# AstroEQ_SMD_MK2_EQ5.net
KiCad netlist of a schematic drawn in EAGLE
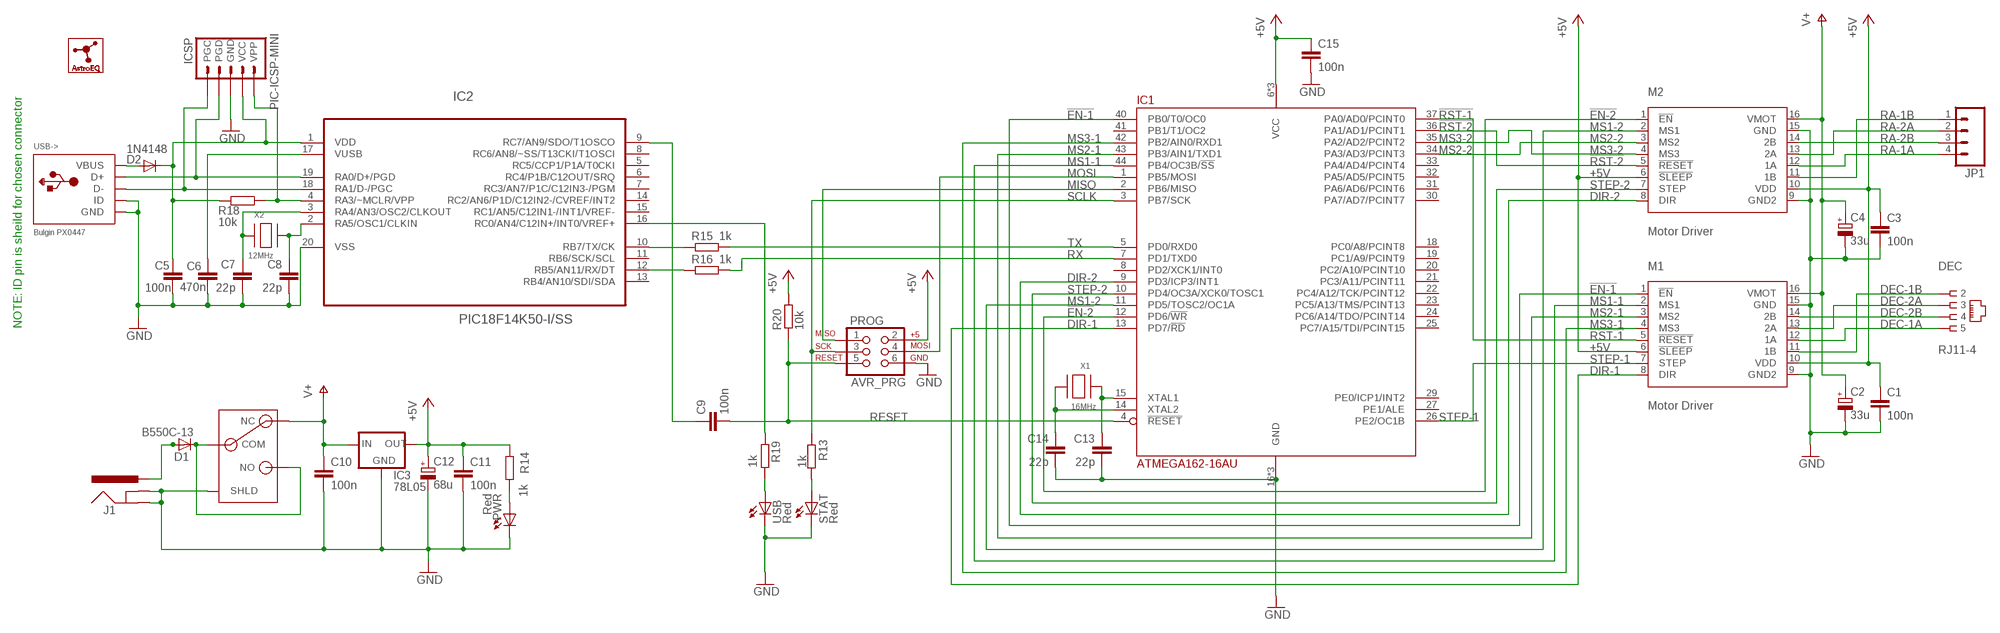
[diagram p0: schematic, sheet 1]

(export (version "E")
  (design (tool "Eeschema 10.0.6"))
  (components
    (comp (ref "C1")
      (value "100n")
      (footprint "eagle-import:C0603")
      (fields (field (name "MF") "MULTICOMP") (field (name "MPN") "T0603F104ZCT"))
      (libsource (lib "eagle-import") (part "resistor_C-EUC0603"))
    )
    (comp (ref "C2")
      (value "33u")
      (footprint "eagle-import:C_6032-28R")
      (fields (field (name "MF") "KEMET") (field (name "MPN") "T491C336K025AT"))
      (libsource (lib "eagle-import") (part "CPOL-EUC/6032-28R"))
    )
    (comp (ref "C3")
      (value "100n")
      (footprint "eagle-import:C0603")
      (fields (field (name "MF") "MULTICOMP") (field (name "MPN") "T0603F104ZCT"))
      (libsource (lib "eagle-import") (part "resistor_C-EUC0603"))
    )
    (comp (ref "C4")
      (value "33u")
      (footprint "eagle-import:C_6032-28R")
      (fields (field (name "MF") "KEMET") (field (name "MPN") "T491C336K025AT"))
      (libsource (lib "eagle-import") (part "CPOL-EUC/6032-28R"))
    )
    (comp (ref "C5")
      (value "100n")
      (footprint "eagle-import:C0603")
      (fields (field (name "MF") "MULTICOMP") (field (name "MPN") "T0603F104ZCT"))
      (libsource (lib "eagle-import") (part "resistor_C-EUC0603"))
    )
    (comp (ref "C6")
      (value "470n")
      (footprint "eagle-import:C0603")
      (fields (field (name "MF") "MURATA") (field (name "MPN") "GRM188R61C474KA93D"))
      (libsource (lib "eagle-import") (part "C-EUC0603"))
    )
    (comp (ref "C7")
      (value "22p")
      (footprint "eagle-import:C0603")
      (fields (field (name "MF") "MULTICOMP") (field (name "MPN") "U0603C220JCT"))
      (libsource (lib "eagle-import") (part "C-EUC0603"))
    )
    (comp (ref "C8")
      (value "22p")
      (footprint "eagle-import:C0603")
      (fields (field (name "MF") "MULTICOMP") (field (name "MPN") "U0603C220JCT"))
      (libsource (lib "eagle-import") (part "C-EUC0603"))
    )
    (comp (ref "C9")
      (value "100n")
      (footprint "eagle-import:C0603")
      (fields (field (name "MF") "MULTICOMP") (field (name "MPN") "T0603F104ZCT"))
      (libsource (lib "eagle-import") (part "resistor_C-EUC0603"))
    )
    (comp (ref "C10")
      (value "100n")
      (footprint "eagle-import:C0603")
      (fields (field (name "MF") "MULTICOMP") (field (name "MPN") "T0603F104ZCT"))
      (libsource (lib "eagle-import") (part "resistor_C-EUC0603"))
    )
    (comp (ref "C11")
      (value "100n")
      (footprint "eagle-import:C0603")
      (fields (field (name "MF") "MULTICOMP") (field (name "MPN") "T0603F104ZCT"))
      (libsource (lib "eagle-import") (part "resistor_C-EUC0603"))
    )
    (comp (ref "C12")
      (value "68u")
      (footprint "eagle-import:C_6032-28R")
      (fields (field (name "MF") "AVX") (field (name "MPN") "TPSC686K016R0125"))
      (libsource (lib "eagle-import") (part "CPOL-EUC/6032-28R"))
    )
    (comp (ref "C13")
      (value "22p")
      (footprint "eagle-import:C0603")
      (fields (field (name "MF") "MULTICOMP") (field (name "MPN") "U0603C220JCT"))
      (libsource (lib "eagle-import") (part "C-EUC0603"))
    )
    (comp (ref "C14")
      (value "22p")
      (footprint "eagle-import:C0603")
      (fields (field (name "MF") "MULTICOMP") (field (name "MPN") "U0603C220JCT"))
      (libsource (lib "eagle-import") (part "C-EUC0603"))
    )
    (comp (ref "C15")
      (value "100n")
      (footprint "eagle-import:C0603")
      (fields (field (name "MF") "MULTICOMP") (field (name "MPN") "T0603F104ZCT"))
      (libsource (lib "eagle-import") (part "resistor_C-EUC0603"))
    )
    (comp (ref "D1")
      (value "B550C-13")
      (footprint "eagle-import:SMC")
      (fields (field (name "MF") "DIODES INC.") (field (name "MPN") "B550C-13-F"))
      (libsource (lib "eagle-import") (part "DIODE-SMC"))
    )
    (comp (ref "D2")
      (value "1N4148")
      (footprint "eagle-import:SOD-323")
      (fields (field (name "MF") "VISHAY SEMICONDUCTOR") (field (name "MPN") "1N4148WS-V-GS08"))
      (libsource (lib "eagle-import") (part "DIODESOD"))
    )
    (comp (ref "DEC")
      (value "RJ11-4")
      (footprint "eagle-import:RJ11-NO_SHIELD-4")
      (fields (field (name "MF") "MOLEX") (field (name "MPN") "95503-2641"))
      (libsource (lib "eagle-import") (part "RJ11-4"))
    )
    (comp (ref "IC1")
      (value "ATMEGA162-16AU")
      (footprint "eagle-import:TQFP44")
      (fields (field (name "MF") "ATMEL"))
      (libsource (lib "eagle-import") (part "ATMEGA162-16AU"))
    )
    (comp (ref "IC2")
      (value "PIC18F14K50-I/SS")
      (footprint "eagle-import:SS20")
      (fields
        (field (name "MPN") "PIC18F14K50")
        (field (name "MF") "MICROCHIP")
        (field (name "MPN_1") "PIC18F14K50-I/SS")
        (field (name "OC_FARNELL") "1648504")
        (field (name "PACKAGE") "SSOP20")
      )
      (libsource (lib "eagle-import") (part "PIC18F14K50-I/SS"))
    )
    (comp (ref "IC3")
      (value "78L05")
      (footprint "eagle-import:SOT23")
      (fields (field (name "MF") "TAIWAN SEMICONDUCTOR") (field (name "MPN") "TS78L05CX RF"))
      (libsource (lib "eagle-import") (part "78LXXSOT-23"))
    )
    (comp (ref "ICSP")
      (value "PIC-ICSP-MINI")
      (footprint "eagle-import:PIC-ICSP-MINI")
      (fields (field (name "MF") "HARWIN") (field (name "MPN") "M52-5000545"))
      (libsource (lib "eagle-import") (part "PIC-ICSP-MINI"))
    )
    (comp (ref "J1")
      (value "POWER_JACKPANEL")
      (footprint "eagle-import:POWER_JACK_PANEL")
      (fields (field (name "MF") "SWITCHCRAFT") (field (name "MPN") "PCL712AS"))
      (libsource (lib "eagle-import") (part "POWER_JACKPANEL"))
    )
    (comp (ref "JP1")
      (value "M04POLAR")
      (footprint "eagle-import:MOLEX-1X4")
      (fields (field (name "MF") "MULTICOMP") (field (name "MPN") "MC34645"))
      (libsource (lib "eagle-import") (part "M04POLAR"))
    )
    (comp (ref "LOGO1")
      (value "ASTROEQ5MM")
      (footprint "eagle-import:ASTROEQ-SMALL")
      (libsource (lib "eagle-import") (part "ASTROEQ5MM"))
    )
    (comp (ref "M1")
      (value "Motor Driver")
      (footprint "eagle-import:DIP16-W")
      (libsource (lib "eagle-import") (part "A4983CARRIER"))
    )
    (comp (ref "M2")
      (value "Motor Driver")
      (footprint "eagle-import:DIP16-W")
      (libsource (lib "eagle-import") (part "A4983CARRIER"))
    )
    (comp (ref "PROG")
      (value "AVR_PRG")
      (footprint "eagle-import:2X3")
      (fields (field (name "MF") "TE CONNECTIVITY / AMP") (field (name "MPN") "826632-3"))
      (libsource (lib "eagle-import") (part "AVR_SPI_PRG_6PTH"))
    )
    (comp (ref "PWR")
      (value "Red")
      (footprint "eagle-import:LED3MM")
      (fields (field (name "MF") "KINGBRIGHT") (field (name "MPN") "L-424HDT"))
      (libsource (lib "eagle-import") (part "LED3MM"))
    )
    (comp (ref "R13")
      (value "1k")
      (footprint "eagle-import:R0603")
      (fields (field (name "MF") "PANASONIC") (field (name "MPN") "ERJ3GEYJ102V"))
      (libsource (lib "eagle-import") (part "rcl_R-EU_R0603"))
    )
    (comp (ref "R14")
      (value "1k")
      (footprint "eagle-import:R0603")
      (fields (field (name "MF") "PANASONIC") (field (name "MPN") "ERJ3GEYJ102V"))
      (libsource (lib "eagle-import") (part "rcl_R-EU_R0603"))
    )
    (comp (ref "R15")
      (value "1k")
      (footprint "eagle-import:R0603")
      (fields (field (name "MF") "PANASONIC") (field (name "MPN") "ERJ3GEYJ102V"))
      (libsource (lib "eagle-import") (part "R-EU_R0603"))
    )
    (comp (ref "R16")
      (value "1k")
      (footprint "eagle-import:R0603")
      (fields (field (name "MF") "PANASONIC") (field (name "MPN") "ERJ3GEYJ102V"))
      (libsource (lib "eagle-import") (part "R-EU_R0603"))
    )
    (comp (ref "R18")
      (value "10k")
      (footprint "eagle-import:R0603")
      (fields (field (name "MF") "PANASONIC") (field (name "MPN") "ERJ3GEYJ103V"))
      (libsource (lib "eagle-import") (part "rcl_R-EU_R0603"))
    )
    (comp (ref "R19")
      (value "1k")
      (footprint "eagle-import:R0603")
      (fields (field (name "MF") "PANASONIC") (field (name "MPN") "ERJ3GEYJ102V"))
      (libsource (lib "eagle-import") (part "rcl_R-EU_R0603"))
    )
    (comp (ref "R20")
      (value "10k")
      (footprint "eagle-import:R0603")
      (fields (field (name "MF") "PANASONIC") (field (name "MPN") "ERJ3GEYJ103V"))
      (libsource (lib "eagle-import") (part "rcl_R-EU_R0603"))
    )
    (comp (ref "STAT")
      (value "Red")
      (footprint "eagle-import:LED3MM")
      (fields (field (name "MF") "KINGBRIGHT") (field (name "MPN") "L-424HDT"))
      (libsource (lib "eagle-import") (part "LED3MM"))
    )
    (comp (ref "SW1")
      (value "SWITCH")
      (footprint "eagle-import:SPST")
      (fields (field (name "MF") "TE CONNECTIVITY") (field (name "MPN") "AE101J1V3B004"))
      (libsource (lib "eagle-import") (part "SWITCH"))
    )
    (comp (ref "USB")
      (value "Red")
      (footprint "eagle-import:LED3MM")
      (fields (field (name "MF") "KINGBRIGHT") (field (name "MPN") "L-424HDT"))
      (libsource (lib "eagle-import") (part "LED3MM"))
    )
    (comp (ref "USB->")
      (value "Bulgin PX0447")
      (footprint "eagle-import:USB-MINIB-BULGIN")
      (fields (field (name "MF") "BULGIN") (field (name "MPN") "PX0447"))
      (libsource (lib "eagle-import") (part "USBBULGIN"))
    )
    (comp (ref "X1")
      (value "16MHz")
      (footprint "eagle-import:NX5032")
      (fields (field (name "MF") "TXC") (field (name "MPN") "7A-16.000MAAJ-T"))
      (libsource (lib "eagle-import") (part "XTALNX5032"))
    )
    (comp (ref "X2")
      (value "12MHz")
      (footprint "eagle-import:NX5032")
      (fields (field (name "MF") "TXC") (field (name "MPN") "7A-12.000MAAJ-T"))
      (libsource (lib "eagle-import") (part "XTALNX5032"))
    )
  )
  (nets
    (net (code "1") (name "+5V") (class "Default")
      (node (ref "C1") (pin "1") (pinfunction "1_1") (pintype "passive"))
      (node (ref "C11") (pin "1") (pinfunction "1_1") (pintype "passive"))
      (node (ref "C12") (pin "+") (pinfunction "+_+") (pintype "passive"))
      (node (ref "C15") (pin "1") (pinfunction "1_1") (pintype "passive"))
      (node (ref "C3") (pin "1") (pinfunction "1_1") (pintype "passive"))
      (node (ref "IC1") (pin "17") (pinfunction "VCC_17") (pintype "power_in"))
      (node (ref "IC1") (pin "38") (pinfunction "VCC_38") (pintype "power_in"))
      (node (ref "IC1") (pin "6") (pinfunction "VCC_6") (pintype "power_in"))
      (node (ref "IC3") (pin "1") (pinfunction "OUT_1") (pintype "passive"))
      (node (ref "M1") (pin "10") (pinfunction "VDD_10") (pintype "power_in"))
      (node (ref "M1") (pin "6") (pinfunction "~{SLEEP}_6") (pintype "input"))
      (node (ref "M2") (pin "10") (pinfunction "VDD_10") (pintype "power_in"))
      (node (ref "M2") (pin "6") (pinfunction "~{SLEEP}_6") (pintype "input"))
      (node (ref "PROG") (pin "2") (pinfunction "2_2") (pintype "passive"))
      (node (ref "R14") (pin "1") (pinfunction "1_1") (pintype "passive"))
      (node (ref "R20") (pin "2") (pinfunction "2_2") (pintype "passive"))
    )
    (net (code "2") (name "/DEC-1A") (class "Default")
      (node (ref "DEC") (pin "5") (pinfunction "5_5") (pintype "passive"))
      (node (ref "M1") (pin "12") (pinfunction "1A_12") (pintype "output"))
    )
    (net (code "3") (name "/DEC-1B") (class "Default")
      (node (ref "DEC") (pin "2") (pinfunction "2_2") (pintype "passive"))
      (node (ref "M1") (pin "11") (pinfunction "1B_11") (pintype "output"))
    )
    (net (code "4") (name "/DEC-2A") (class "Default")
      (node (ref "DEC") (pin "3") (pinfunction "3_3") (pintype "passive"))
      (node (ref "M1") (pin "13") (pinfunction "2A_13") (pintype "output"))
    )
    (net (code "5") (name "/DEC-2B") (class "Default")
      (node (ref "DEC") (pin "4") (pinfunction "4_4") (pintype "passive"))
      (node (ref "M1") (pin "14") (pinfunction "2B_14") (pintype "output"))
    )
    (net (code "6") (name "/DIR-1") (class "Default")
      (node (ref "IC1") (pin "13") (pinfunction "PD7/~{RD}_13") (pintype "bidirectional"))
      (node (ref "M1") (pin "8") (pinfunction "DIR_8") (pintype "input"))
    )
    (net (code "7") (name "/DIR-2") (class "Default")
      (node (ref "IC1") (pin "9") (pinfunction "PD3/ICP3/INT1_9") (pintype "bidirectional"))
      (node (ref "M2") (pin "8") (pinfunction "DIR_8") (pintype "input"))
    )
    (net (code "8") (name "/MISO") (class "Default")
      (node (ref "IC1") (pin "2") (pinfunction "PB6/MISO_2") (pintype "bidirectional"))
      (node (ref "PROG") (pin "1") (pinfunction "1_1") (pintype "passive"))
    )
    (net (code "9") (name "/MOSI") (class "Default")
      (node (ref "IC1") (pin "1") (pinfunction "PB5/MOSI_1") (pintype "bidirectional"))
      (node (ref "PROG") (pin "4") (pinfunction "4_4") (pintype "passive"))
    )
    (net (code "10") (name "/MS1-1") (class "Default")
      (node (ref "IC1") (pin "44") (pinfunction "PB4/OC3B/~{SS}_44") (pintype "bidirectional"))
      (node (ref "M1") (pin "2") (pinfunction "MS1_2") (pintype "input"))
    )
    (net (code "11") (name "/MS1-2") (class "Default")
      (node (ref "IC1") (pin "11") (pinfunction "PD5/TOSC2/OC1A_11") (pintype "bidirectional"))
      (node (ref "M2") (pin "2") (pinfunction "MS1_2") (pintype "input"))
    )
    (net (code "12") (name "/MS2-1") (class "Default")
      (node (ref "IC1") (pin "43") (pinfunction "PB3/AIN1/TXD1_43") (pintype "bidirectional"))
      (node (ref "M1") (pin "3") (pinfunction "MS2_3") (pintype "input"))
    )
    (net (code "13") (name "/MS2-2") (class "Default")
      (node (ref "IC1") (pin "34") (pinfunction "PA3/AD3/PCINT3_34") (pintype "bidirectional"))
      (node (ref "M2") (pin "3") (pinfunction "MS2_3") (pintype "input"))
    )
    (net (code "14") (name "/MS3-1") (class "Default")
      (node (ref "IC1") (pin "42") (pinfunction "PB2/AIN0/RXD1_42") (pintype "bidirectional"))
      (node (ref "M1") (pin "4") (pinfunction "MS3_4") (pintype "input"))
    )
    (net (code "15") (name "/MS3-2") (class "Default")
      (node (ref "IC1") (pin "35") (pinfunction "PA2/AD2/PCINT2_35") (pintype "bidirectional"))
      (node (ref "M2") (pin "4") (pinfunction "MS3_4") (pintype "input"))
    )
    (net (code "16") (name "/RA-1A") (class "Default")
      (node (ref "JP1") (pin "4") (pinfunction "4_4") (pintype "passive"))
      (node (ref "M2") (pin "12") (pinfunction "1A_12") (pintype "output"))
    )
    (net (code "17") (name "/RA-1B") (class "Default")
      (node (ref "JP1") (pin "1") (pinfunction "1_1") (pintype "passive"))
      (node (ref "M2") (pin "11") (pinfunction "1B_11") (pintype "output"))
    )
    (net (code "18") (name "/RA-2A") (class "Default")
      (node (ref "JP1") (pin "2") (pinfunction "2_2") (pintype "passive"))
      (node (ref "M2") (pin "13") (pinfunction "2A_13") (pintype "output"))
    )
    (net (code "19") (name "/RA-2B") (class "Default")
      (node (ref "JP1") (pin "3") (pinfunction "3_3") (pintype "passive"))
      (node (ref "M2") (pin "14") (pinfunction "2B_14") (pintype "output"))
    )
    (net (code "20") (name "/RESET") (class "Default")
      (node (ref "C9") (pin "2") (pinfunction "2_2") (pintype "passive"))
      (node (ref "IC1") (pin "4") (pinfunction "~{RESET}_4") (pintype "input"))
      (node (ref "PROG") (pin "5") (pinfunction "5_5") (pintype "passive"))
      (node (ref "R20") (pin "1") (pinfunction "1_1") (pintype "passive"))
    )
    (net (code "21") (name "/RX") (class "Default")
      (node (ref "IC1") (pin "7") (pinfunction "PD1/TXD0_7") (pintype "bidirectional"))
      (node (ref "R16") (pin "1") (pinfunction "1_1") (pintype "passive"))
    )
    (net (code "22") (name "/SCLK") (class "Default")
      (node (ref "IC1") (pin "3") (pinfunction "PB7/SCK_3") (pintype "bidirectional"))
      (node (ref "PROG") (pin "3") (pinfunction "3_3") (pintype "passive"))
      (node (ref "R13") (pin "1") (pinfunction "1_1") (pintype "passive"))
    )
    (net (code "23") (name "/STEP-1") (class "Default")
      (node (ref "IC1") (pin "26") (pinfunction "PE2/OC1B_26") (pintype "bidirectional"))
      (node (ref "M1") (pin "7") (pinfunction "STEP_7") (pintype "input"))
    )
    (net (code "24") (name "/STEP-2") (class "Default")
      (node (ref "IC1") (pin "10") (pinfunction "PD4/OC3A/XCK0/TOSC1_10") (pintype "bidirectional"))
      (node (ref "M2") (pin "7") (pinfunction "STEP_7") (pintype "input"))
    )
    (net (code "25") (name "/TX") (class "Default")
      (node (ref "IC1") (pin "5") (pinfunction "PD0/RXD0_5") (pintype "bidirectional"))
      (node (ref "R15") (pin "1") (pinfunction "1_1") (pintype "passive"))
    )
    (net (code "26") (name "/~{EN-1}") (class "Default")
      (node (ref "IC1") (pin "40") (pinfunction "PB0/T0/OC0_40") (pintype "bidirectional"))
      (node (ref "M1") (pin "1") (pinfunction "~{EN}_1") (pintype "input"))
    )
    (net (code "27") (name "/~{EN-2}") (class "Default")
      (node (ref "IC1") (pin "12") (pinfunction "PD6/~{WR}_12") (pintype "bidirectional"))
      (node (ref "M2") (pin "1") (pinfunction "~{EN}_1") (pintype "input"))
    )
    (net (code "28") (name "/~{RST-1}") (class "Default")
      (node (ref "IC1") (pin "37") (pinfunction "PA0/AD0/PCINT0_37") (pintype "bidirectional"))
      (node (ref "M1") (pin "5") (pinfunction "~{RESET}_5") (pintype "input"))
    )
    (net (code "29") (name "/~{RST-2}") (class "Default")
      (node (ref "IC1") (pin "36") (pinfunction "PA1/AD1/PCINT1_36") (pintype "bidirectional"))
      (node (ref "M2") (pin "5") (pinfunction "~{RESET}_5") (pintype "input"))
    )
    (net (code "30") (name "GND") (class "Default")
      (node (ref "C1") (pin "2") (pinfunction "2_2") (pintype "passive"))
      (node (ref "C10") (pin "2") (pinfunction "2_2") (pintype "passive"))
      (node (ref "C11") (pin "2") (pinfunction "2_2") (pintype "passive"))
      (node (ref "C12") (pin "-") (pinfunction "-_-") (pintype "passive"))
      (node (ref "C13") (pin "2") (pinfunction "2_2") (pintype "passive"))
      (node (ref "C14") (pin "2") (pinfunction "2_2") (pintype "passive"))
      (node (ref "C15") (pin "2") (pinfunction "2_2") (pintype "passive"))
      (node (ref "C2") (pin "-") (pinfunction "-_-") (pintype "passive"))
      (node (ref "C3") (pin "2") (pinfunction "2_2") (pintype "passive"))
      (node (ref "C4") (pin "-") (pinfunction "-_-") (pintype "passive"))
      (node (ref "C5") (pin "2") (pinfunction "2_2") (pintype "passive"))
      (node (ref "C6") (pin "1") (pinfunction "1_1") (pintype "passive"))
      (node (ref "C7") (pin "2") (pinfunction "2_2") (pintype "passive"))
      (node (ref "C8") (pin "2") (pinfunction "2_2") (pintype "passive"))
      (node (ref "IC1") (pin "16") (pinfunction "GND_16") (pintype "power_in"))
      (node (ref "IC1") (pin "28") (pinfunction "GND_28") (pintype "power_in"))
      (node (ref "IC1") (pin "39") (pinfunction "GND_39") (pintype "power_in"))
      (node (ref "IC2") (pin "20") (pinfunction "VSS_20") (pintype "power_in"))
      (node (ref "IC3") (pin "3") (pinfunction "GND_3") (pintype "input"))
      (node (ref "ICSP") (pin "3") (pinfunction "GND_3") (pintype "passive"))
      (node (ref "J1") (pin "SHUNT") (pinfunction "GNDBREAK_SHUNT") (pintype "bidirectional"))
      (node (ref "J1") (pin "SLEEVE") (pinfunction "GND_SLEEVE") (pintype "bidirectional"))
      (node (ref "M1") (pin "15") (pinfunction "GND_15") (pintype "power_in"))
      (node (ref "M1") (pin "9") (pinfunction "GND2_9") (pintype "power_in"))
      (node (ref "M2") (pin "15") (pinfunction "GND_15") (pintype "power_in"))
      (node (ref "M2") (pin "9") (pinfunction "GND2_9") (pintype "power_in"))
      (node (ref "PROG") (pin "6") (pinfunction "6_6") (pintype "passive"))
      (node (ref "PWR") (pin "K") (pinfunction "C_K") (pintype "passive"))
      (node (ref "STAT") (pin "K") (pinfunction "C_K") (pintype "passive"))
      (node (ref "SW1") (pin "S1") (pinfunction "SHLD_S1") (pintype "bidirectional"))
      (node (ref "SW1") (pin "S2") (pinfunction "SHLD_S2") (pintype "bidirectional"))
      (node (ref "SW1") (pin "S3") (pinfunction "SHLD_S3") (pintype "bidirectional"))
      (node (ref "SW1") (pin "S4") (pinfunction "SHLD_S4") (pintype "bidirectional"))
      (node (ref "USB") (pin "K") (pinfunction "C_K") (pintype "passive"))
      (node (ref "USB->") (pin "4") (pinfunction "GND_4") (pintype "power_in"))
      (node (ref "USB->") (pin "5") (pinfunction "ID_5") (pintype "bidirectional"))
    )
    (net (code "31") (name "Net-(D1-PadC)") (class "Default")
      (node (ref "D1") (pin "C") (pinfunction "C_C") (pintype "passive"))
      (node (ref "SW1") (pin "COM") (pinfunction "COM_COM") (pintype "passive"))
      (node (ref "SW1") (pin "NO") (pinfunction "NO_NO") (pintype "passive"))
    )
    (net (code "32") (name "Net-(D2-A)") (class "Default")
      (node (ref "D2") (pin "2") (pinfunction "A_2") (pintype "passive"))
      (node (ref "USB->") (pin "1") (pinfunction "VBUS_1") (pintype "power_in"))
    )
    (net (code "33") (name "Net-(D2-C)") (class "Default")
      (node (ref "C5") (pin "1") (pinfunction "1_1") (pintype "passive"))
      (node (ref "D2") (pin "1") (pinfunction "C_1") (pintype "passive"))
      (node (ref "IC2") (pin "1") (pinfunction "VDD_1") (pintype "power_in"))
      (node (ref "ICSP") (pin "2") (pinfunction "VCC_2") (pintype "passive"))
      (node (ref "R18") (pin "2") (pinfunction "2_2") (pintype "passive"))
    )
    (net (code "34") (name "Net-(IC1-XTAL1)") (class "Default")
      (node (ref "C13") (pin "1") (pinfunction "1_1") (pintype "passive"))
      (node (ref "IC1") (pin "15") (pinfunction "XTAL1_15") (pintype "input"))
      (node (ref "X1") (pin "P$1") (pinfunction "P$1_P$1") (pintype "bidirectional"))
    )
    (net (code "35") (name "Net-(IC1-XTAL2)") (class "Default")
      (node (ref "C14") (pin "1") (pinfunction "1_1") (pintype "passive"))
      (node (ref "IC1") (pin "14") (pinfunction "XTAL2_14") (pintype "input"))
      (node (ref "X1") (pin "P$2") (pinfunction "P$2_P$2") (pintype "bidirectional"))
    )
    (net (code "36") (name "Net-(IC2-RA0{slash}D+{slash}PGD)") (class "Default")
      (node (ref "IC2") (pin "19") (pinfunction "RA0/D+/PGD_19") (pintype "bidirectional"))
      (node (ref "ICSP") (pin "4") (pinfunction "PGD_4") (pintype "passive"))
      (node (ref "USB->") (pin "3") (pinfunction "D+_3") (pintype "bidirectional"))
    )
    (net (code "37") (name "Net-(IC2-RA1{slash}D-{slash}PGC)") (class "Default")
      (node (ref "IC2") (pin "18") (pinfunction "RA1/D-/PGC_18") (pintype "bidirectional"))
      (node (ref "ICSP") (pin "5") (pinfunction "PGC_5") (pintype "passive"))
      (node (ref "USB->") (pin "2") (pinfunction "D-_2") (pintype "bidirectional"))
    )
    (net (code "38") (name "Net-(IC2-RA3{slash}~{MCLR{slash}VPP})") (class "Default")
      (node (ref "IC2") (pin "4") (pinfunction "RA3/~{MCLR/VPP}_4") (pintype "input"))
      (node (ref "ICSP") (pin "1") (pinfunction "VPP_1") (pintype "passive"))
      (node (ref "R18") (pin "1") (pinfunction "1_1") (pintype "passive"))
    )
    (net (code "39") (name "Net-(IC2-RA4{slash}AN3{slash}OSC2{slash}CLKOUT)") (class "Default")
      (node (ref "C7") (pin "1") (pinfunction "1_1") (pintype "passive"))
      (node (ref "IC2") (pin "3") (pinfunction "RA4/AN3/OSC2/CLKOUT_3") (pintype "bidirectional"))
      (node (ref "X2") (pin "P$1") (pinfunction "P$1_P$1") (pintype "bidirectional"))
    )
    (net (code "40") (name "Net-(IC2-RA5{slash}OSC1{slash}CLKIN)") (class "Default")
      (node (ref "C8") (pin "1") (pinfunction "1_1") (pintype "passive"))
      (node (ref "IC2") (pin "2") (pinfunction "RA5/OSC1/CLKIN_2") (pintype "bidirectional"))
      (node (ref "X2") (pin "P$2") (pinfunction "P$2_P$2") (pintype "bidirectional"))
    )
    (net (code "41") (name "Net-(IC2-RB5{slash}AN11{slash}RX{slash}DT)") (class "Default")
      (node (ref "IC2") (pin "12") (pinfunction "RB5/AN11/RX/DT_12") (pintype "bidirectional"))
      (node (ref "R16") (pin "2") (pinfunction "2_2") (pintype "passive"))
    )
    (net (code "42") (name "Net-(IC2-RB7{slash}TX{slash}CK)") (class "Default")
      (node (ref "IC2") (pin "10") (pinfunction "RB7/TX/CK_10") (pintype "bidirectional"))
      (node (ref "R15") (pin "2") (pinfunction "2_2") (pintype "passive"))
    )
    (net (code "43") (name "Net-(IC2-RC0{slash}AN4{slash}C12IN+{slash}INT0{slash}VREF+)") (class "Default")
      (node (ref "IC2") (pin "16") (pinfunction "RC0/AN4/C12IN+/INT0/VREF+_16") (pintype "bidirectional"))
      (node (ref "R19") (pin "2") (pinfunction "2_2") (pintype "passive"))
    )
    (net (code "44") (name "Net-(IC2-RC7{slash}AN9{slash}SDO{slash}T1OSCO)") (class "Default")
      (node (ref "C9") (pin "1") (pinfunction "1_1") (pintype "passive"))
      (node (ref "IC2") (pin "9") (pinfunction "RC7/AN9/SDO/T1OSCO_9") (pintype "bidirectional"))
    )
    (net (code "45") (name "Net-(IC2-VUSB)") (class "Default")
      (node (ref "C6") (pin "2") (pinfunction "2_2") (pintype "passive"))
      (node (ref "IC2") (pin "17") (pinfunction "VUSB_17") (pintype "power_in"))
    )
    (net (code "46") (name "Net-(J1-PWR)") (class "Default")
      (node (ref "D1") (pin "A") (pinfunction "A_A") (pintype "passive"))
      (node (ref "J1") (pin "CENTRE") (pinfunction "PWR_CENTRE") (pintype "bidirectional"))
    )
    (net (code "47") (name "Net-(PWR-PadA)") (class "Default")
      (node (ref "PWR") (pin "A") (pinfunction "A_A") (pintype "passive"))
      (node (ref "R14") (pin "2") (pinfunction "2_2") (pintype "passive"))
    )
    (net (code "48") (name "Net-(R13-Pad2)") (class "Default")
      (node (ref "R13") (pin "2") (pinfunction "2_2") (pintype "passive"))
      (node (ref "STAT") (pin "A") (pinfunction "A_A") (pintype "passive"))
    )
    (net (code "49") (name "Net-(R19-Pad1)") (class "Default")
      (node (ref "R19") (pin "1") (pinfunction "1_1") (pintype "passive"))
      (node (ref "USB") (pin "A") (pinfunction "A_A") (pintype "passive"))
    )
    (net (code "50") (name "V+") (class "Default")
      (node (ref "C10") (pin "1") (pinfunction "1_1") (pintype "passive"))
      (node (ref "C2") (pin "+") (pinfunction "+_+") (pintype "passive"))
      (node (ref "C4") (pin "+") (pinfunction "+_+") (pintype "passive"))
      (node (ref "IC3") (pin "2") (pinfunction "IN_2") (pintype "input"))
      (node (ref "M1") (pin "16") (pinfunction "VMOT_16") (pintype "power_in"))
      (node (ref "M2") (pin "16") (pinfunction "VMOT_16") (pintype "power_in"))
      (node (ref "SW1") (pin "NC") (pinfunction "NC_NC") (pintype "passive"))
    )
    (net (code "51") (name "unconnected-(IC1-PA4{slash}AD4{slash}PCINT4-Pad33)") (class "Default")
      (node (ref "IC1") (pin "33") (pinfunction "PA4/AD4/PCINT4_33") (pintype "bidirectional"))
    )
    (net (code "52") (name "unconnected-(IC1-PA5{slash}AD5{slash}PCINT5-Pad32)") (class "Default")
      (node (ref "IC1") (pin "32") (pinfunction "PA5/AD5/PCINT5_32") (pintype "bidirectional"))
    )
    (net (code "53") (name "unconnected-(IC1-PA6{slash}AD6{slash}PCINT6-Pad31)") (class "Default")
      (node (ref "IC1") (pin "31") (pinfunction "PA6/AD6/PCINT6_31") (pintype "bidirectional"))
    )
    (net (code "54") (name "unconnected-(IC1-PA7{slash}AD7{slash}PCINT7-Pad30)") (class "Default")
      (node (ref "IC1") (pin "30") (pinfunction "PA7/AD7/PCINT7_30") (pintype "bidirectional"))
    )
    (net (code "55") (name "unconnected-(IC1-PB1{slash}T1{slash}OC2-Pad41)") (class "Default")
      (node (ref "IC1") (pin "41") (pinfunction "PB1/T1/OC2_41") (pintype "bidirectional"))
    )
    (net (code "56") (name "unconnected-(IC1-PC0{slash}A8{slash}PCINT8-Pad18)") (class "Default")
      (node (ref "IC1") (pin "18") (pinfunction "PC0/A8/PCINT8_18") (pintype "bidirectional"))
    )
    (net (code "57") (name "unconnected-(IC1-PC1{slash}A9{slash}PCINT9-Pad19)") (class "Default")
      (node (ref "IC1") (pin "19") (pinfunction "PC1/A9/PCINT9_19") (pintype "bidirectional"))
    )
    (net (code "58") (name "unconnected-(IC1-PC2{slash}A10{slash}PCINT10-Pad20)") (class "Default")
      (node (ref "IC1") (pin "20") (pinfunction "PC2/A10/PCINT10_20") (pintype "bidirectional"))
    )
    (net (code "59") (name "unconnected-(IC1-PC3{slash}A11{slash}PCINT11-Pad21)") (class "Default")
      (node (ref "IC1") (pin "21") (pinfunction "PC3/A11/PCINT11_21") (pintype "bidirectional"))
    )
    (net (code "60") (name "unconnected-(IC1-PC4{slash}A12{slash}TCK{slash}PCINT12-Pad22)") (class "Default")
      (node (ref "IC1") (pin "22") (pinfunction "PC4/A12/TCK/PCINT12_22") (pintype "bidirectional"))
    )
    (net (code "61") (name "unconnected-(IC1-PC5{slash}A13{slash}TMS{slash}PCINT13-Pad23)") (class "Default")
      (node (ref "IC1") (pin "23") (pinfunction "PC5/A13/TMS/PCINT13_23") (pintype "bidirectional"))
    )
    (net (code "62") (name "unconnected-(IC1-PC6{slash}A14{slash}TDO{slash}PCINT14-Pad24)") (class "Default")
      (node (ref "IC1") (pin "24") (pinfunction "PC6/A14/TDO/PCINT14_24") (pintype "bidirectional"))
    )
    (net (code "63") (name "unconnected-(IC1-PC7{slash}A15{slash}TDI{slash}PCINT15-Pad25)") (class "Default")
      (node (ref "IC1") (pin "25") (pinfunction "PC7/A15/TDI/PCINT15_25") (pintype "bidirectional"))
    )
    (net (code "64") (name "unconnected-(IC1-PD2{slash}XCK1{slash}INT0-Pad8)") (class "Default")
      (node (ref "IC1") (pin "8") (pinfunction "PD2/XCK1/INT0_8") (pintype "bidirectional"))
    )
    (net (code "65") (name "unconnected-(IC1-PE0{slash}ICP1{slash}INT2-Pad29)") (class "Default")
      (node (ref "IC1") (pin "29") (pinfunction "PE0/ICP1/INT2_29") (pintype "bidirectional"))
    )
    (net (code "66") (name "unconnected-(IC1-PE1{slash}ALE-Pad27)") (class "Default")
      (node (ref "IC1") (pin "27") (pinfunction "PE1/ALE_27") (pintype "bidirectional"))
    )
    (net (code "67") (name "unconnected-(IC2-RB4{slash}AN10{slash}SDI{slash}SDA-Pad13)") (class "Default")
      (node (ref "IC2") (pin "13") (pinfunction "RB4/AN10/SDI/SDA_13") (pintype "bidirectional"))
    )
    (net (code "68") (name "unconnected-(IC2-RB6{slash}SCK{slash}SCL-Pad11)") (class "Default")
      (node (ref "IC2") (pin "11") (pinfunction "RB6/SCK/SCL_11") (pintype "bidirectional"))
    )
    (net (code "69") (name "unconnected-(IC2-RC1{slash}AN5{slash}C12IN1-{slash}INT1{slash}VREF--Pad15)") (class "Default")
      (node (ref "IC2") (pin "15") (pinfunction "RC1/AN5/C12IN1-/INT1/VREF-_15") (pintype "bidirectional"))
    )
    (net (code "70") (name "unconnected-(IC2-RC2{slash}AN6{slash}P1D{slash}C12IN2-{slash}CVREF{slash}INT2-Pad14)") (class "Default")
      (node (ref "IC2") (pin "14") (pinfunction "RC2/AN6/P1D/C12IN2-/CVREF/INT2_14") (pintype "bidirectional"))
    )
    (net (code "71") (name "unconnected-(IC2-RC3{slash}AN7{slash}P1C{slash}C12IN3-{slash}PGM-Pad7)") (class "Default")
      (node (ref "IC2") (pin "7") (pinfunction "RC3/AN7/P1C/C12IN3-/PGM_7") (pintype "bidirectional"))
    )
    (net (code "72") (name "unconnected-(IC2-RC4{slash}P1B{slash}C12OUT{slash}SRQ-Pad6)") (class "Default")
      (node (ref "IC2") (pin "6") (pinfunction "RC4/P1B/C12OUT/SRQ_6") (pintype "bidirectional"))
    )
    (net (code "73") (name "unconnected-(IC2-RC5{slash}CCP1{slash}P1A{slash}T0CKI-Pad5)") (class "Default")
      (node (ref "IC2") (pin "5") (pinfunction "RC5/CCP1/P1A/T0CKI_5") (pintype "bidirectional"))
    )
    (net (code "74") (name "unconnected-(IC2-RC6{slash}AN8{slash}~{SS{slash}T13CKI{slash}T1OSCI}-Pad8)") (class "Default")
      (node (ref "IC2") (pin "8") (pinfunction "RC6/AN8/~{SS/T13CKI/T1OSCI}_8") (pintype "bidirectional"))
    )
  )
)
